# pickup.net
KiCad netlist of a schematic drawn in EasyEDA
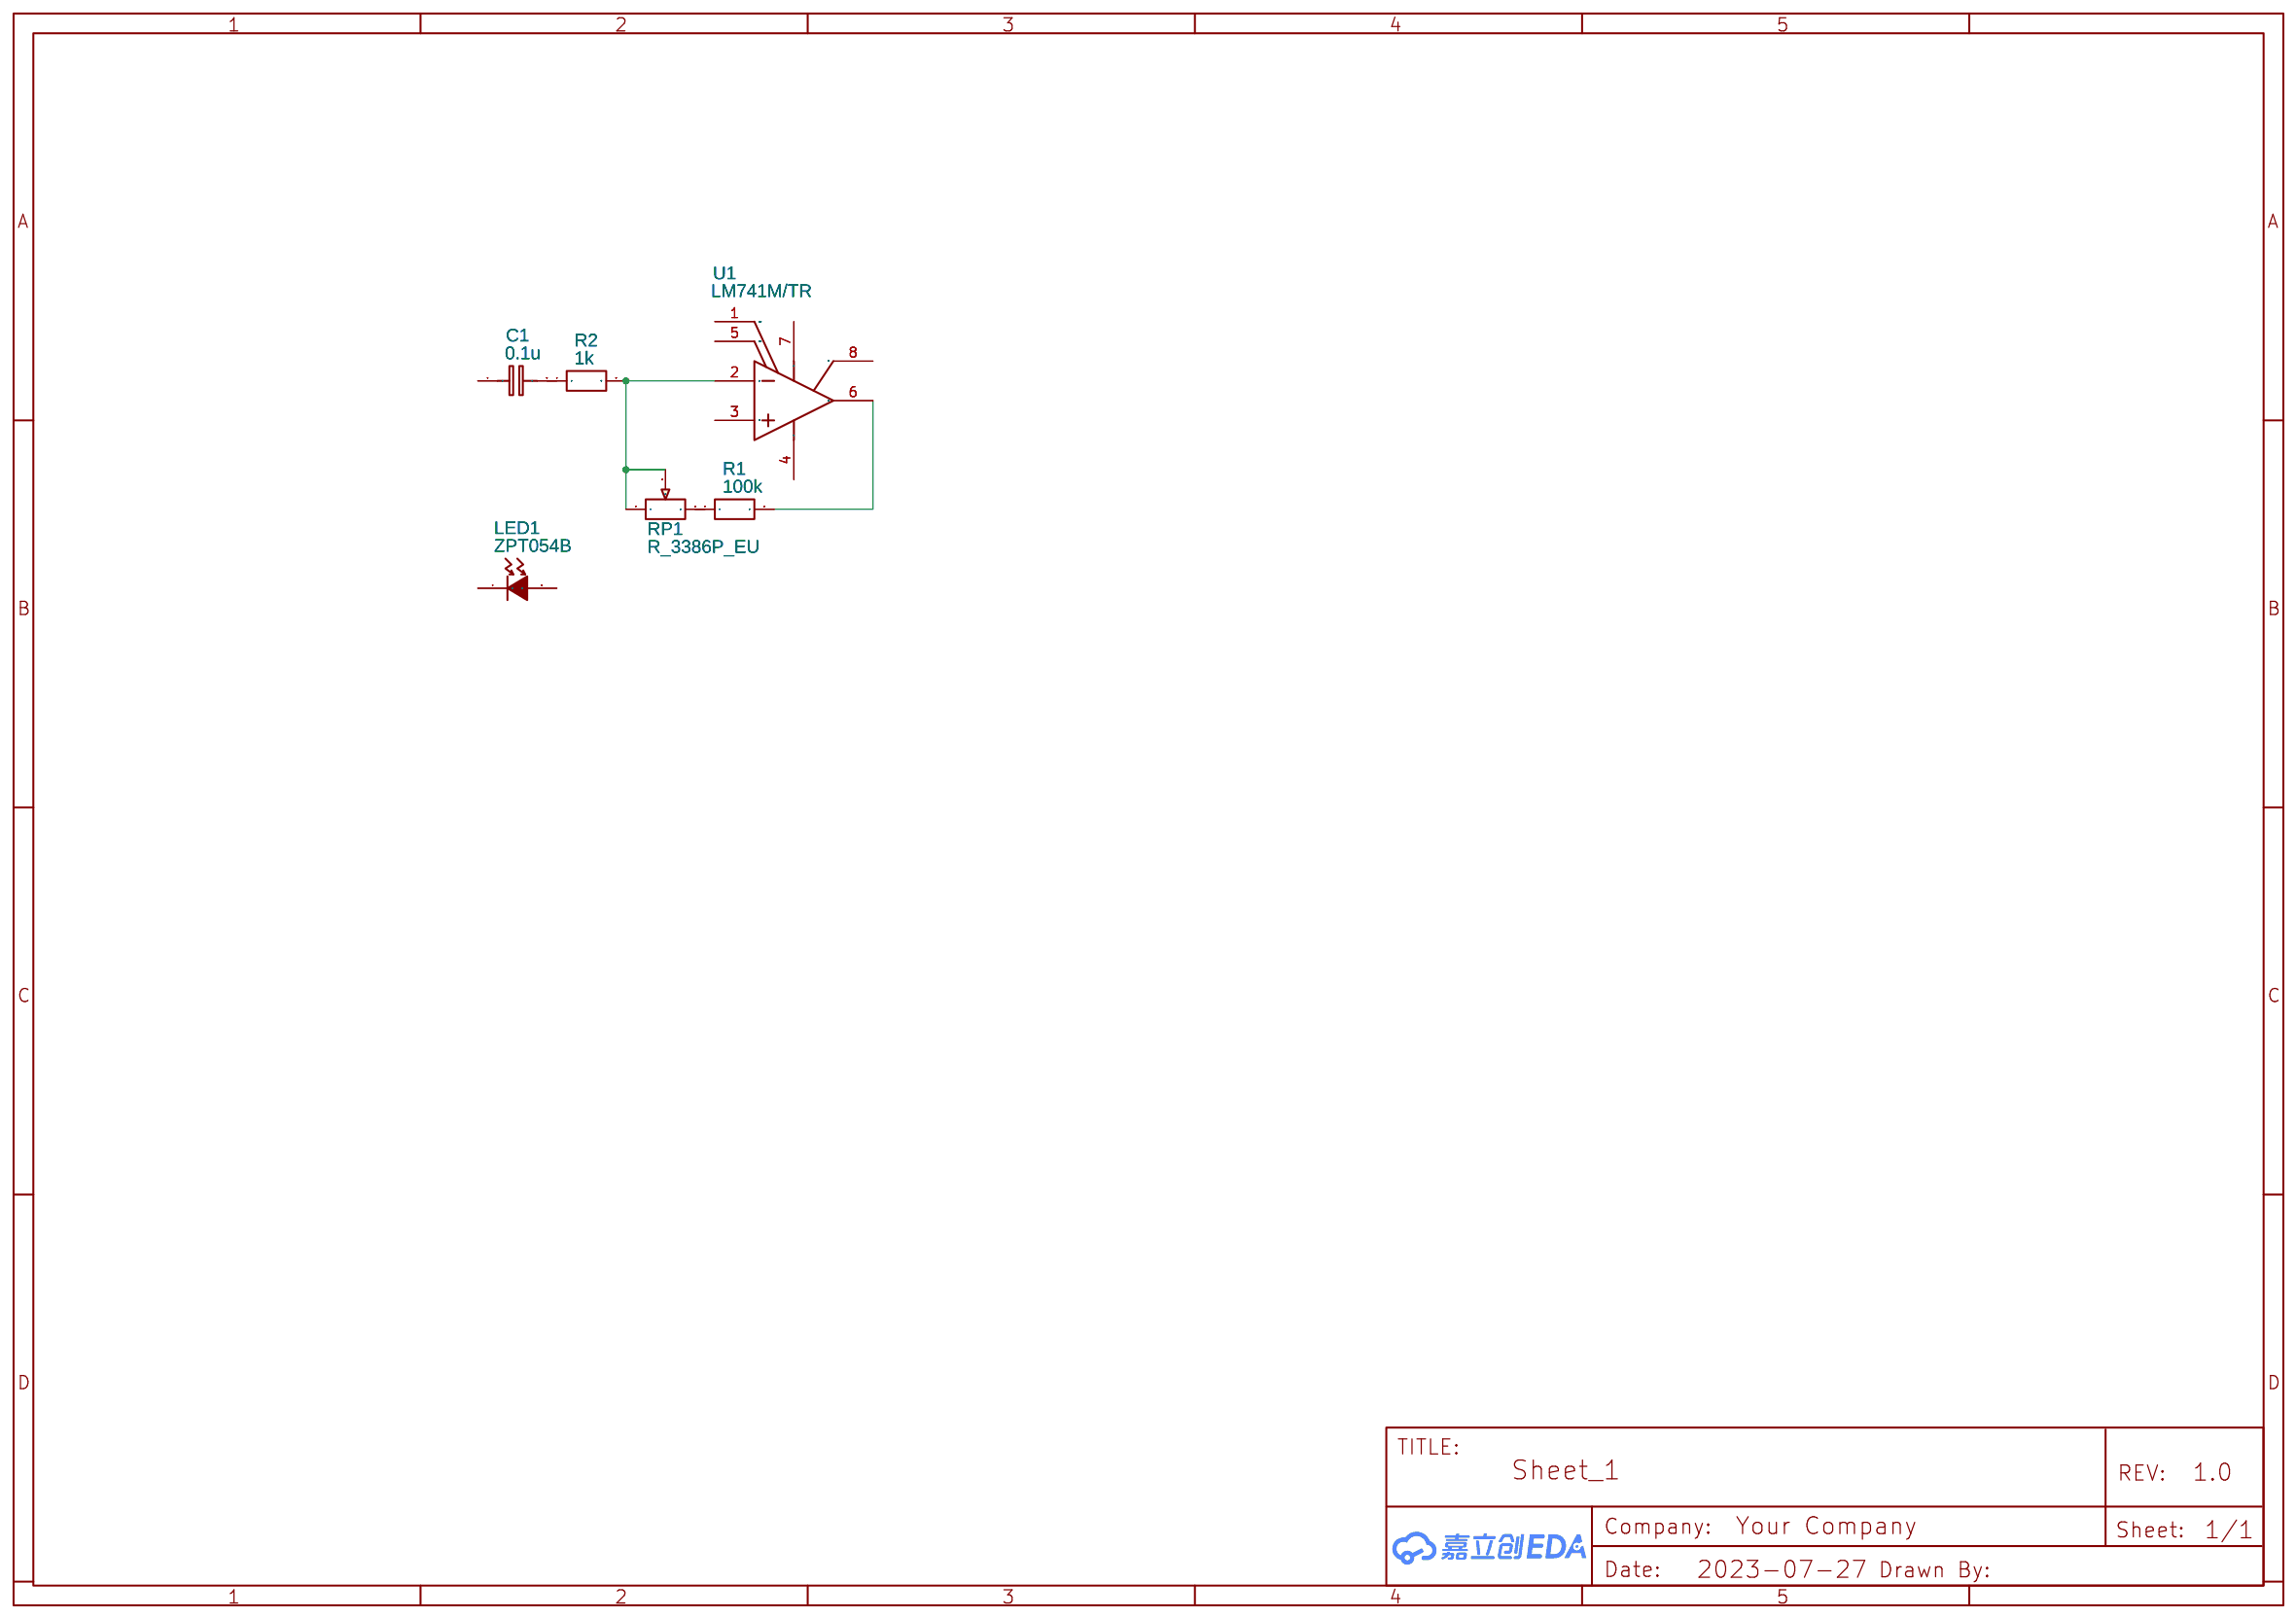
[diagram p0: schematic sheet]

(export (version "E")
  (design (tool "Eeschema 10.0.6"))
  (components
    (comp (ref "C1") (value "0.1u") (libsource (lib "") (part "C_0603_EU")))
    (comp (ref "LED1")
      (value "ZPT054B")
      (fields (field (name "Manufacturer") "Chau Light"))
      (libsource (lib "") (part "ZPT054B"))
    )
    (comp (ref "R1") (value "100k") (libsource (lib "") (part "R_0603_EU")))
    (comp (ref "R2") (value "1k") (libsource (lib "") (part "R_0603_EU")))
    (comp (ref "RP1") (value "R_3386P_EU") (libsource (lib "") (part "R_3386P_EU")))
    (comp (ref "U1")
      (value "LM741M/TR")
      (fields (field (name "Manufacturer") "HGSEMI(华冠)"))
      (libsource (lib "") (part "LM741M/TR"))
    )
  )
  (nets
    (net (code "1") (name "Net-(U1-IN-)") (class "Default")
      (node (ref "R2") (pin "2") (pinfunction "2_2") (pintype "unspecified"))
      (node (ref "RP1") (pin "1") (pinfunction "1_1") (pintype "input"))
      (node (ref "RP1") (pin "2") (pinfunction "2_2") (pintype "input"))
      (node (ref "U1") (pin "2") (pinfunction "IN-_2") (pintype "unspecified"))
    )
    (net (code "2") (name "Net-(U1-OUT)") (class "Default")
      (node (ref "R1") (pin "2") (pinfunction "2_2") (pintype "unspecified"))
      (node (ref "U1") (pin "6") (pinfunction "OUT_6") (pintype "output"))
    )
    (net (code "3") (name "unconnected-(C1-Pad1)") (class "Default")
      (node (ref "C1") (pin "1") (pinfunction "1_1") (pintype "unspecified"))
    )
    (net (code "4") (name "unconnected-(C1-Pad2)") (class "Default")
      (node (ref "C1") (pin "2") (pinfunction "2_2") (pintype "unspecified"))
    )
    (net (code "5") (name "unconnected-(LED1-C-Pad2)") (class "Default")
      (node (ref "LED1") (pin "2") (pinfunction "C_2") (pintype "input"))
    )
    (net (code "6") (name "unconnected-(LED1-E-Pad1)") (class "Default")
      (node (ref "LED1") (pin "1") (pinfunction "E_1") (pintype "input"))
    )
    (net (code "7") (name "unconnected-(R1-Pad1)") (class "Default")
      (node (ref "R1") (pin "1") (pinfunction "1_1") (pintype "unspecified"))
    )
    (net (code "8") (name "unconnected-(R2-Pad1)") (class "Default")
      (node (ref "R2") (pin "1") (pinfunction "1_1") (pintype "unspecified"))
    )
    (net (code "9") (name "unconnected-(RP1-Pad3)") (class "Default")
      (node (ref "RP1") (pin "3") (pinfunction "3_3") (pintype "input"))
    )
    (net (code "10") (name "unconnected-(U1-IN+-Pad3)") (class "Default")
      (node (ref "U1") (pin "3") (pinfunction "IN+_3") (pintype "unspecified"))
    )
    (net (code "11") (name "unconnected-(U1-NC-Pad8)") (class "Default")
      (node (ref "U1") (pin "8") (pinfunction "NC_8") (pintype "unspecified"))
    )
    (net (code "12") (name "unconnected-(U1-OFFSET_NULL-Pad1)") (class "Default")
      (node (ref "U1") (pin "1") (pinfunction "OFFSET_NULL_1") (pintype "unspecified"))
    )
    (net (code "13") (name "unconnected-(U1-OFFSET_NULL-Pad5)") (class "Default")
      (node (ref "U1") (pin "5") (pinfunction "OFFSET_NULL_5") (pintype "unspecified"))
    )
    (net (code "14") (name "unconnected-(U1-V+-Pad7)") (class "Default")
      (node (ref "U1") (pin "7") (pinfunction "V+_7") (pintype "passive"))
    )
    (net (code "15") (name "unconnected-(U1-V--Pad4)") (class "Default")
      (node (ref "U1") (pin "4") (pinfunction "V-_4") (pintype "passive"))
    )
  )
)
